# NT_RadioModule_wurx.net
KiCad netlist of a schematic drawn in EAGLE
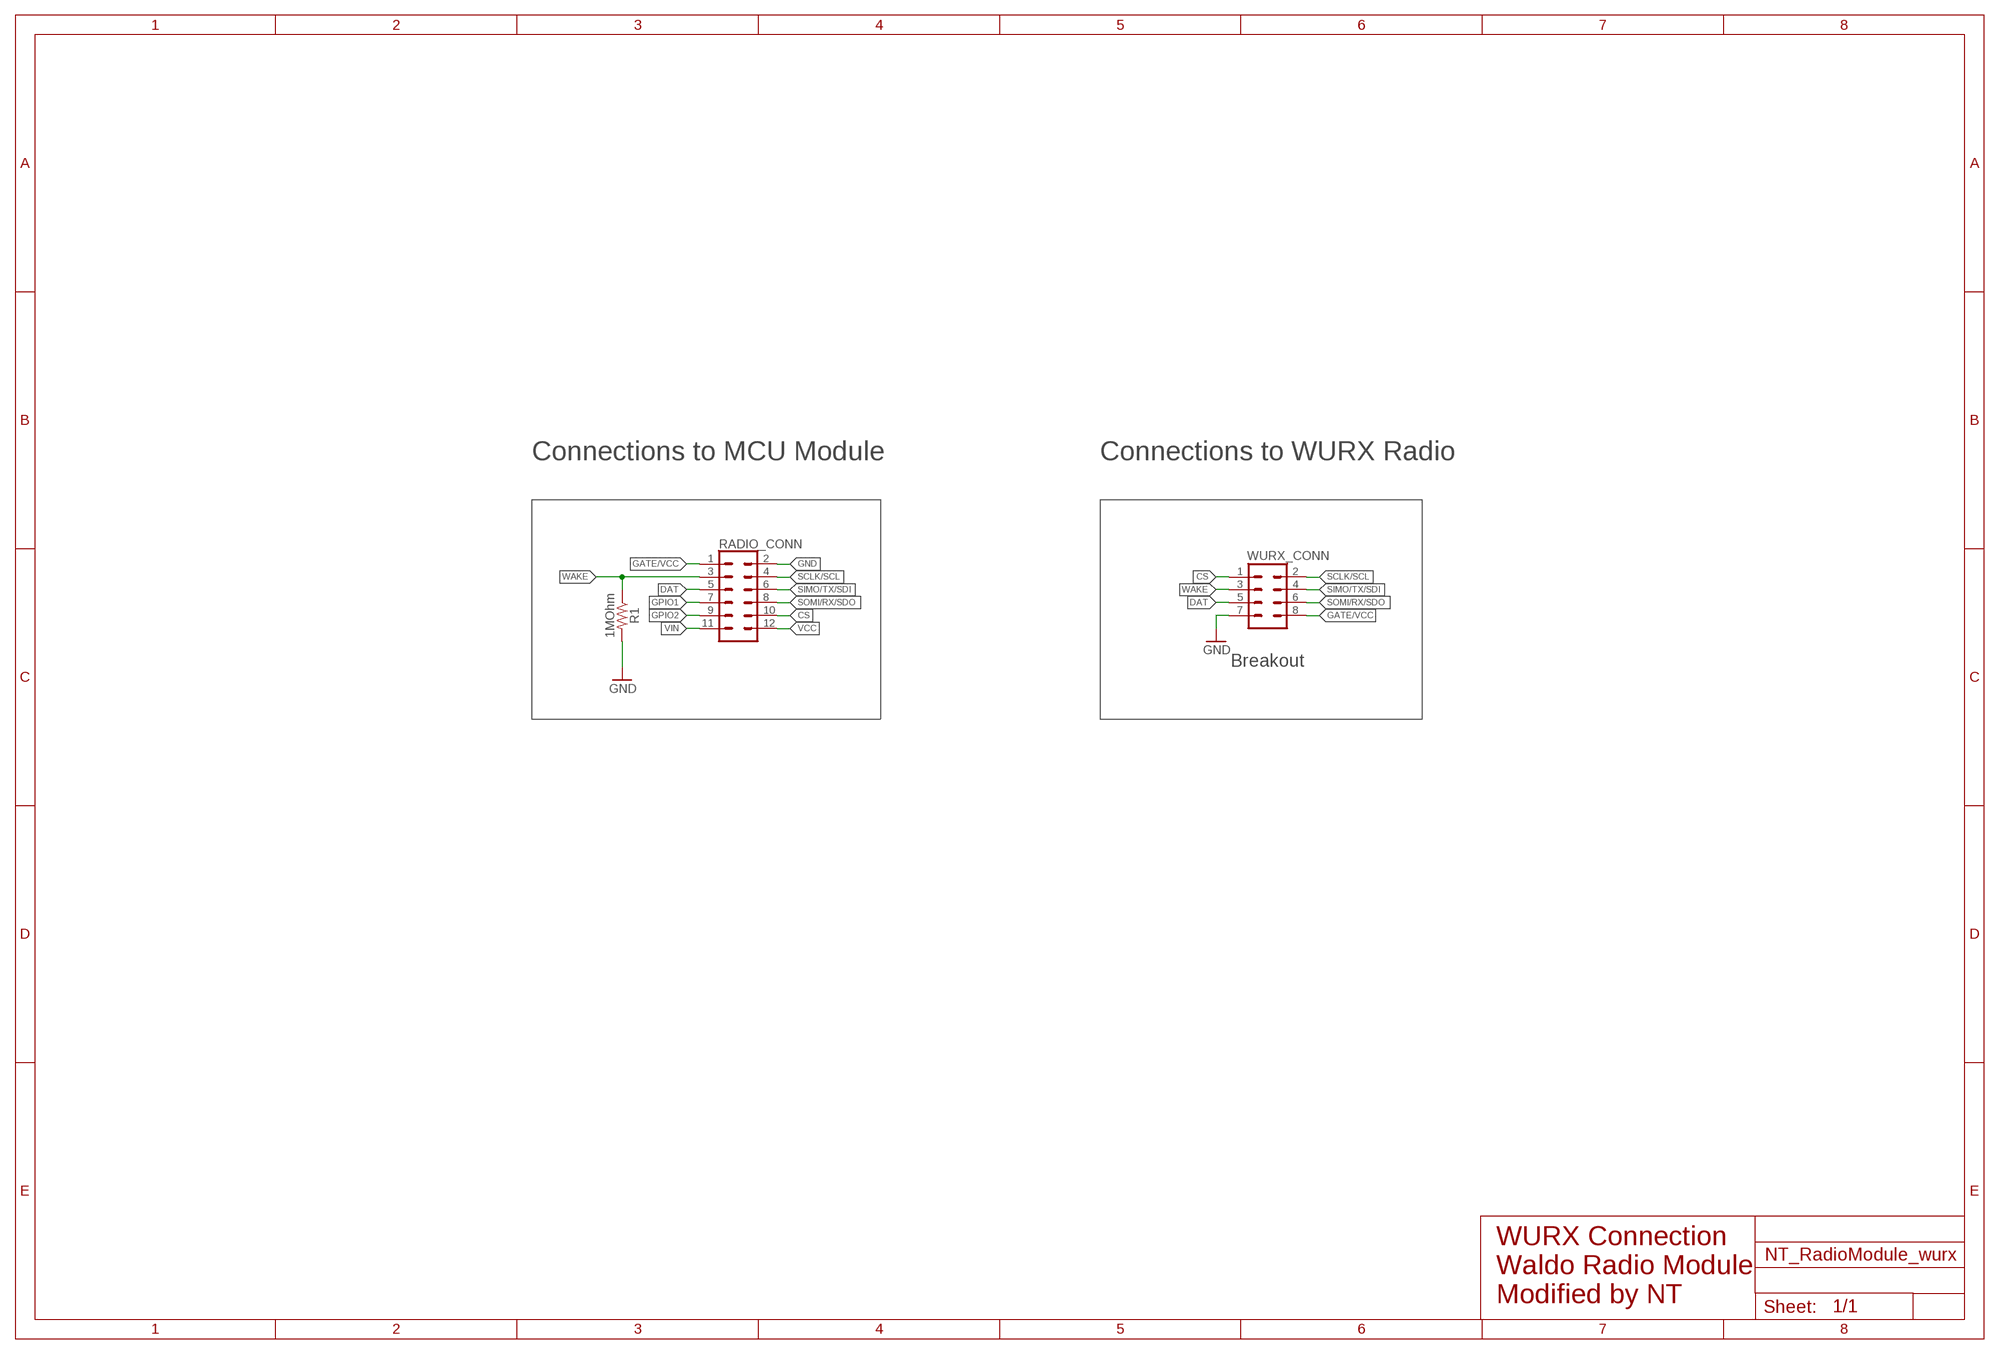
[diagram p0: schematic, sheet 1]

(export (version "E")
  (design (tool "Eeschema 10.0.6"))
  (components
    (comp (ref "R1")
      (value "1MOhm")
      (footprint "eagle-import:0805")
      (libsource (lib "eagle-import") (part "0.3OHM-0805-1/8W-1%"))
    )
    (comp (ref "RADIO_CONN")
      (value "CONN_06X2PTH_FEMALE")
      (footprint "eagle-import:2X6")
      (libsource (lib "eagle-import") (part "CONN_06X2PTH_FEMALE"))
    )
    (comp (ref "WURX_CONN")
      (value "M04X2")
      (footprint "eagle-import:2X4")
      (libsource (lib "eagle-import") (part "M04X2"))
    )
  )
  (nets
    (net (code "1") (name "CS") (class "Default")
      (node (ref "RADIO_CONN") (pin "10") (pinfunction "10_10") (pintype "passive"))
      (node (ref "WURX_CONN") (pin "1") (pinfunction "1_1") (pintype "passive"))
    )
    (net (code "2") (name "DAT") (class "Default")
      (node (ref "RADIO_CONN") (pin "5") (pinfunction "5_5") (pintype "passive"))
      (node (ref "WURX_CONN") (pin "5") (pinfunction "5_5") (pintype "passive"))
    )
    (net (code "3") (name "GATE{slash}VCC") (class "Default")
      (node (ref "RADIO_CONN") (pin "1") (pinfunction "1_1") (pintype "passive"))
      (node (ref "WURX_CONN") (pin "8") (pinfunction "8_8") (pintype "passive"))
    )
    (net (code "4") (name "GND") (class "Default")
      (node (ref "R1") (pin "2") (pinfunction "2_2") (pintype "passive"))
      (node (ref "RADIO_CONN") (pin "2") (pinfunction "2_2") (pintype "passive"))
      (node (ref "WURX_CONN") (pin "7") (pinfunction "7_7") (pintype "passive"))
    )
    (net (code "5") (name "GPIO1") (class "Default")
      (node (ref "RADIO_CONN") (pin "7") (pinfunction "7_7") (pintype "passive"))
    )
    (net (code "6") (name "GPIO2") (class "Default")
      (node (ref "RADIO_CONN") (pin "9") (pinfunction "9_9") (pintype "passive"))
    )
    (net (code "7") (name "SCLK{slash}SCL") (class "Default")
      (node (ref "RADIO_CONN") (pin "4") (pinfunction "4_4") (pintype "passive"))
      (node (ref "WURX_CONN") (pin "2") (pinfunction "2_2") (pintype "passive"))
    )
    (net (code "8") (name "SIMO{slash}TX{slash}SDI") (class "Default")
      (node (ref "RADIO_CONN") (pin "6") (pinfunction "6_6") (pintype "passive"))
      (node (ref "WURX_CONN") (pin "4") (pinfunction "4_4") (pintype "passive"))
    )
    (net (code "9") (name "SOMI{slash}RX{slash}SDO") (class "Default")
      (node (ref "RADIO_CONN") (pin "8") (pinfunction "8_8") (pintype "passive"))
      (node (ref "WURX_CONN") (pin "6") (pinfunction "6_6") (pintype "passive"))
    )
    (net (code "10") (name "VCC") (class "Default")
      (node (ref "RADIO_CONN") (pin "12") (pinfunction "12_12") (pintype "passive"))
    )
    (net (code "11") (name "VIN") (class "Default")
      (node (ref "RADIO_CONN") (pin "11") (pinfunction "11_11") (pintype "passive"))
    )
    (net (code "12") (name "WAKE") (class "Default")
      (node (ref "R1") (pin "1") (pinfunction "1_1") (pintype "passive"))
      (node (ref "RADIO_CONN") (pin "3") (pinfunction "3_3") (pintype "passive"))
      (node (ref "WURX_CONN") (pin "3") (pinfunction "3_3") (pintype "passive"))
    )
  )
)
